# 5V_Supply.net
KiCad netlist of a schematic drawn in Altium Designer
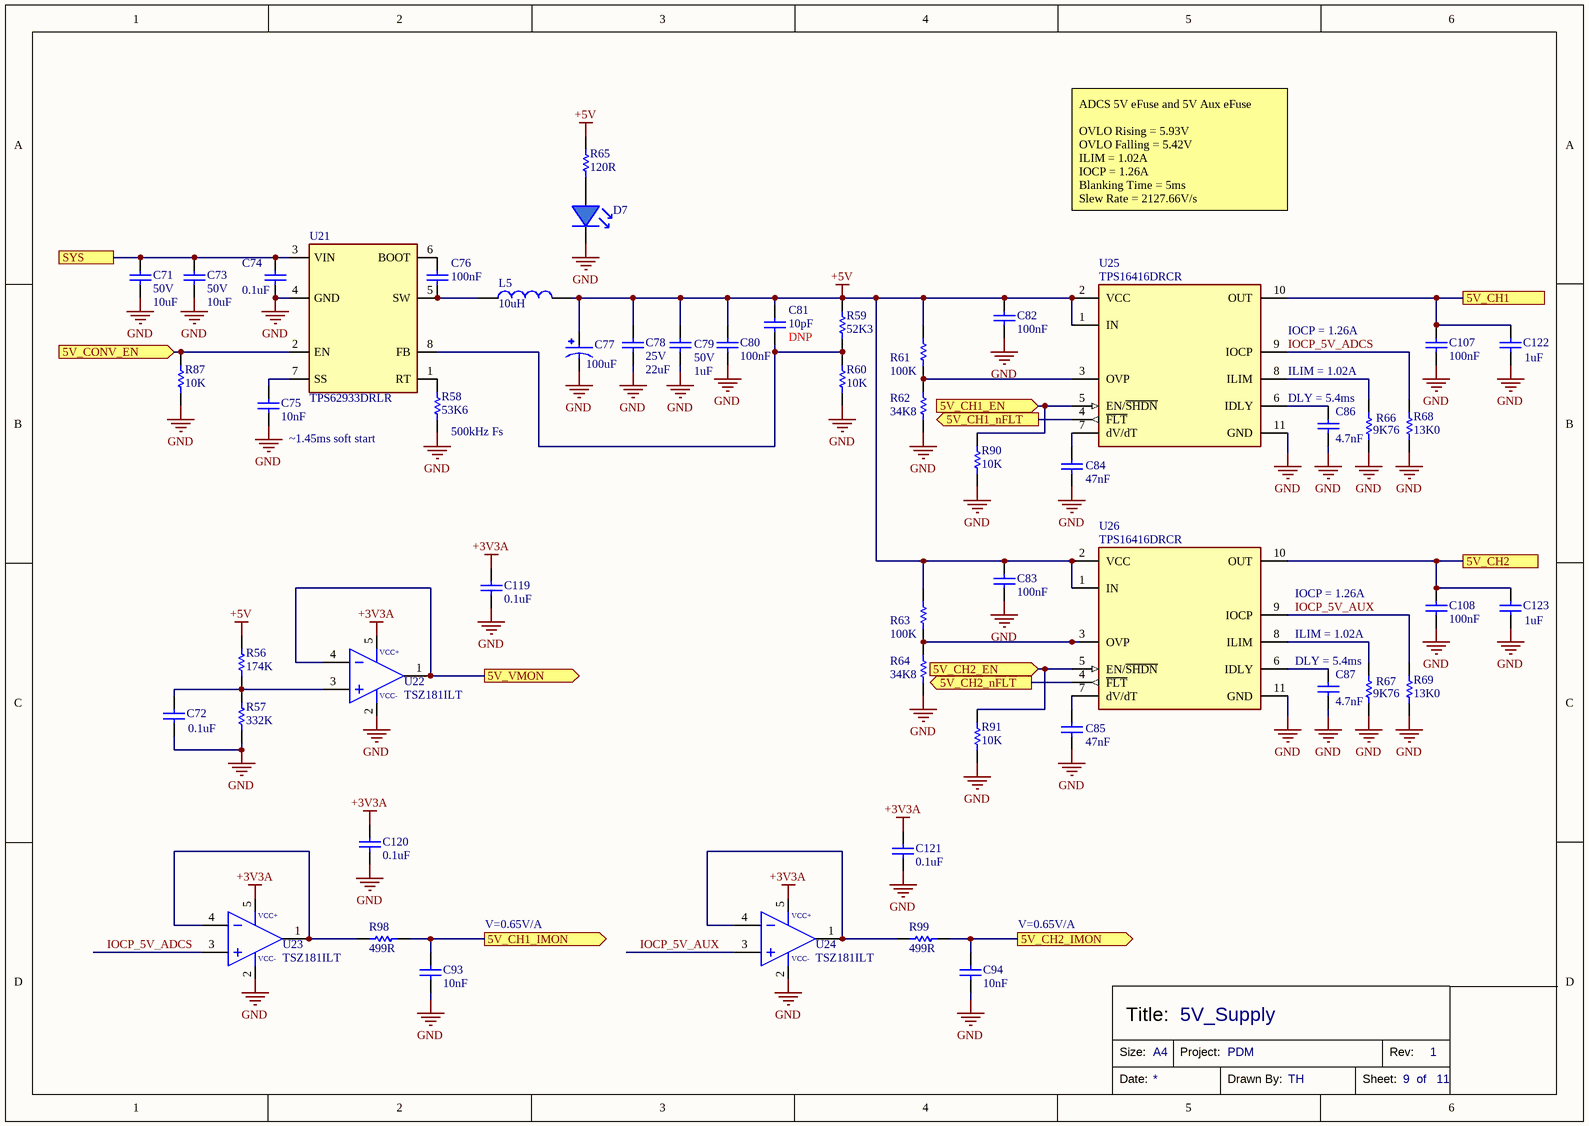
[diagram p0: 5V_Supply.SchDoc]

(export (version "E")
  (design (tool "Eeschema 10.0.6"))
  (components
    (comp (ref "C71")
      (value "CL32B106KBJNNNE")
      (footprint "CAPC1210X090")
      (description "10 µF ±10% 50V Ceramic Capacitor X7R 1210 (3225 Metric)")
      (fields
        (field (name "DISTRIBUTOR PART NUMBER") "1276-3387-1-ND")
        (field (name "TOLERANCE") "10%")
        (field (name "VOLTAGE RATING") "50V")
        (field (name "CAPACITANCE") "10uF")
      )
      (libsource (lib "Ahristi_Library") (part "CL32B106KBJNNNE"))
    )
    (comp (ref "C72")
      (value "CL21B104KACNNNC")
      (footprint "CAPC0805X060")
      (description "0.1uF ±10% 25V Ceramic Capacitor X7R 0805 (2012 Metric)")
      (fields
        (field (name "DISTRIBUTOR PART NUMBER") "1276-1099-1-ND")
        (field (name "TOLERANCE") "10%")
        (field (name "CAPACITANCE") "0.1uF")
      )
      (libsource (lib "Ahristi_Library") (part "CL21B104KACNNNC"))
    )
    (comp (ref "C73")
      (value "CL32B106KBJNNNE")
      (footprint "CAPC1210X090")
      (description "10 µF ±10% 50V Ceramic Capacitor X7R 1210 (3225 Metric)")
      (fields
        (field (name "DISTRIBUTOR PART NUMBER") "1276-3387-1-ND")
        (field (name "TOLERANCE") "10%")
        (field (name "VOLTAGE RATING") "50V")
        (field (name "CAPACITANCE") "10uF")
      )
      (libsource (lib "Ahristi_Library") (part "CL32B106KBJNNNE"))
    )
    (comp (ref "C74")
      (value "CL05B104KB5NNNC")
      (footprint "CAPC0402X020")
      (description "0.1 µF ±10% 50V Ceramic Capacitor X7R 0402 (1005 Metric)")
      (fields
        (field (name "TOLERANCE") "10%")
        (field (name "DISTRIBUTOR PART NUMBER") "1276-CL05B104KB5NNNCCT-ND")
        (field (name "CAPACITANCE") "0.1uF")
      )
      (libsource (lib "Ahristi_Library") (part "CL05B104KB5NNNC"))
    )
    (comp (ref "C75")
      (value "CL21B103KBANNNC")
      (footprint "CAPC0805X060")
      (description "10nF ±10% 50V Ceramic Capacitor X7R 0805 (2012 Metric)")
      (fields
        (field (name "DISTRIBUTOR PART NUMBER") "1276-1015-1-ND")
        (field (name "TOLERANCE") "10%")
        (field (name "CAPACITANCE") "10nF")
      )
      (libsource (lib "Ahristi_Library") (part "CL21B103KBANNNC"))
    )
    (comp (ref "C76")
      (value "C0603C104K5RACTU")
      (footprint "CAPC0603X040")
      (description "0.1 µF ±10% 50V Ceramic Capacitor X7R 0603 (1608 Metric)")
      (fields
        (field (name "DISTRIBUTOR PART NUMBER") "399-C0603C104K5RACTUCT-ND")
        (field (name "TOLERANCE") "10%")
        (field (name "CAPACITANCE") "100nF")
      )
      (libsource (lib "Ahristi_Library") (part "C0603C104K5RACTU"))
    )
    (comp (ref "C77")
      (value "TPSC107K010R0100")
      (footprint "2312 Tantalum")
      (description "100 µF Molded Tantalum Capacitors 10 V 2312 (6032 Metric) 100mOhm")
      (fields (field (name "DISTRIBUTOR PART NUMBER") "478-1765-1-ND") (field (name "CAPACITANCE") "100uF"))
      (libsource (lib "Ahristi_Library") (part "TPSC107K010R0100"))
    )
    (comp (ref "C78")
      (value "CL32B226KAJNNNE")
      (footprint "CAPC1210X090")
      (description "22 µF ±10% 25V Ceramic Capacitor X7R 1210 (3225 Metric)")
      (fields
        (field (name "DISTRIBUTOR PART NUMBER") "1276-3392-1-ND")
        (field (name "TOLERANCE") "10%")
        (field (name "VOLTAGE RATING") "25V")
        (field (name "CAPACITANCE") "22uF")
      )
      (libsource (lib "Ahristi_Library") (part "CL32B226KAJNNNE"))
    )
    (comp (ref "C79")
      (value "CL21B105KBFNNNE")
      (footprint "CAPC0805X060")
      (description "1uF 50V X7R ±10% 0805 Multilayer Ceramic Capacitors MLCC - SMD/SMT ROHS")
      (fields
        (field (name "DISTRIBUTOR PART NUMBER") "1276-1029-1-ND")
        (field (name "TOLERANCE") "10%")
        (field (name "VOLTAGE RATING") "50V")
        (field (name "CAPACITANCE") "1uF")
      )
      (libsource (lib "Ahristi_Library") (part "CL21B105KBFNNNE"))
    )
    (comp (ref "C80")
      (value "C0603C104K5RACTU")
      (footprint "CAPC0603X040")
      (description "0.1 µF ±10% 50V Ceramic Capacitor X7R 0603 (1608 Metric)")
      (fields
        (field (name "DISTRIBUTOR PART NUMBER") "399-C0603C104K5RACTUCT-ND")
        (field (name "TOLERANCE") "10%")
        (field (name "CAPACITANCE") "100nF")
      )
      (libsource (lib "Ahristi_Library") (part "C0603C104K5RACTU"))
    )
    (comp (ref "C81")
      (value "C0603C104K5RACTU")
      (footprint "CAPC0603X040")
      (description "10 pF ±5% 50V Ceramic Capacitor C0G, NP0 0603 (1608 Metric)")
      (fields
        (field (name "PART NUMBER") "C0603C100J5GACTU")
        (field (name "DISTRIBUTOR PART NUMBER") "399-C0603C100J5GACTUCT-ND")
        (field (name "CAPACITANCE") "10pF")
      )
      (libsource (lib "Ahristi_Library") (part "C0603C100J5GACTU"))
    )
    (comp (ref "C82")
      (value "C0603C104K5RACTU")
      (footprint "CAPC0603X040")
      (description "0.1 µF ±10% 50V Ceramic Capacitor X7R 0603 (1608 Metric)")
      (fields
        (field (name "DISTRIBUTOR PART NUMBER") "399-C0603C104K5RACTUCT-ND")
        (field (name "TOLERANCE") "10%")
        (field (name "CAPACITANCE") "100nF")
      )
      (libsource (lib "Ahristi_Library") (part "C0603C104K5RACTU"))
    )
    (comp (ref "C83")
      (value "C0603C104K5RACTU")
      (footprint "CAPC0603X040")
      (description "0.1 µF ±10% 50V Ceramic Capacitor X7R 0603 (1608 Metric)")
      (fields
        (field (name "DISTRIBUTOR PART NUMBER") "399-C0603C104K5RACTUCT-ND")
        (field (name "TOLERANCE") "10%")
        (field (name "CAPACITANCE") "100nF")
      )
      (libsource (lib "Ahristi_Library") (part "C0603C104K5RACTU"))
    )
    (comp (ref "C84")
      (value "CL21B473KBCNNNC")
      (footprint "CAPC0805X060")
      (description "0.047 µF ±10% 50V Ceramic Capacitor X7R 0805 (2012 Metric)")
      (fields
        (field (name "DISTRIBUTOR PART NUMBER") "1276-1250-1-ND")
        (field (name "TOLERANCE") "10%")
        (field (name "CAPACITANCE") "47nF")
      )
      (libsource (lib "Ahristi_Library") (part "CL21B473KBCNNNC"))
    )
    (comp (ref "C85")
      (value "CL21B473KBCNNNC")
      (footprint "CAPC0805X060")
      (description "0.047 µF ±10% 50V Ceramic Capacitor X7R 0805 (2012 Metric)")
      (fields
        (field (name "DISTRIBUTOR PART NUMBER") "1276-1250-1-ND")
        (field (name "TOLERANCE") "10%")
        (field (name "CAPACITANCE") "47nF")
      )
      (libsource (lib "Ahristi_Library") (part "CL21B473KBCNNNC"))
    )
    (comp (ref "C86")
      (value "CL21B105KAFNNNE")
      (footprint "CAPC0805X060")
      (description "4.7nF ±10% 50V Ceramic Capacitor X7R 0805 (2012 Metric)")
      (fields
        (field (name "PART NUMBER") "CL21B472KBANNNC")
        (field (name "DISTRIBUTOR PART NUMBER") "1276-1155-1-ND")
        (field (name "CAPACITANCE") "4.7nF")
      )
      (libsource (lib "Ahristi_Library") (part "CL21B472KBANNNC"))
    )
    (comp (ref "C87")
      (value "CL21B105KAFNNNE")
      (footprint "CAPC0805X060")
      (description "4.7nF ±10% 50V Ceramic Capacitor X7R 0805 (2012 Metric)")
      (fields
        (field (name "PART NUMBER") "CL21B472KBANNNC")
        (field (name "DISTRIBUTOR PART NUMBER") "1276-1155-1-ND")
        (field (name "CAPACITANCE") "4.7nF")
      )
      (libsource (lib "Ahristi_Library") (part "CL21B472KBANNNC"))
    )
    (comp (ref "C93")
      (value "CL21B103KBANNNC")
      (footprint "CAPC0805X060")
      (description "10nF ±10% 50V Ceramic Capacitor X7R 0805 (2012 Metric)")
      (fields
        (field (name "DISTRIBUTOR PART NUMBER") "1276-1015-1-ND")
        (field (name "TOLERANCE") "10%")
        (field (name "CAPACITANCE") "10nF")
      )
      (libsource (lib "Ahristi_Library") (part "CL21B103KBANNNC"))
    )
    (comp (ref "C94")
      (value "CL21B103KBANNNC")
      (footprint "CAPC0805X060")
      (description "10nF ±10% 50V Ceramic Capacitor X7R 0805 (2012 Metric)")
      (fields
        (field (name "DISTRIBUTOR PART NUMBER") "1276-1015-1-ND")
        (field (name "TOLERANCE") "10%")
        (field (name "CAPACITANCE") "10nF")
      )
      (libsource (lib "Ahristi_Library") (part "CL21B103KBANNNC"))
    )
    (comp (ref "C107")
      (value "C0603C104K5RACTU")
      (footprint "CAPC0603X040")
      (description "0.1 µF ±10% 50V Ceramic Capacitor X7R 0603 (1608 Metric)")
      (fields
        (field (name "DISTRIBUTOR PART NUMBER") "399-C0603C104K5RACTUCT-ND")
        (field (name "TOLERANCE") "10%")
        (field (name "CAPACITANCE") "100nF")
      )
      (libsource (lib "Ahristi_Library") (part "C0603C104K5RACTU"))
    )
    (comp (ref "C108")
      (value "C0603C104K5RACTU")
      (footprint "CAPC0603X040")
      (description "0.1 µF ±10% 50V Ceramic Capacitor X7R 0603 (1608 Metric)")
      (fields
        (field (name "DISTRIBUTOR PART NUMBER") "399-C0603C104K5RACTUCT-ND")
        (field (name "TOLERANCE") "10%")
        (field (name "CAPACITANCE") "100nF")
      )
      (libsource (lib "Ahristi_Library") (part "C0603C104K5RACTU"))
    )
    (comp (ref "C119")
      (value "C0603C104K5RACTU")
      (footprint "CAPC0603X040")
      (description "0.1 µF ±10% 50V Ceramic Capacitor X7R 0603 (1608 Metric)")
      (fields
        (field (name "DISTRIBUTOR PART NUMBER") "399-C0603C104K5RACTUCT-ND")
        (field (name "TOLERANCE") "10%")
        (field (name "CAPACITANCE") "0.1uF")
      )
      (libsource (lib "Ahristi_Library") (part "C0603C104K5RACTU"))
    )
    (comp (ref "C120")
      (value "C0603C104K5RACTU")
      (footprint "CAPC0603X040")
      (description "0.1 µF ±10% 50V Ceramic Capacitor X7R 0603 (1608 Metric)")
      (fields
        (field (name "DISTRIBUTOR PART NUMBER") "399-C0603C104K5RACTUCT-ND")
        (field (name "TOLERANCE") "10%")
        (field (name "CAPACITANCE") "0.1uF")
      )
      (libsource (lib "Ahristi_Library") (part "C0603C104K5RACTU"))
    )
    (comp (ref "C121")
      (value "C0603C104K5RACTU")
      (footprint "CAPC0603X040")
      (description "0.1 µF ±10% 50V Ceramic Capacitor X7R 0603 (1608 Metric)")
      (fields
        (field (name "DISTRIBUTOR PART NUMBER") "399-C0603C104K5RACTUCT-ND")
        (field (name "TOLERANCE") "10%")
        (field (name "CAPACITANCE") "0.1uF")
      )
      (libsource (lib "Ahristi_Library") (part "C0603C104K5RACTU"))
    )
    (comp (ref "C122")
      (value "CL21B105KAFNNNE")
      (footprint "CAPC0805X060")
      (description "1uF ±10% 25V Ceramic Capacitor X7R 0805 (2012 Metric)")
      (fields
        (field (name "DISTRIBUTOR PART NUMBER") "1276-1066-1-ND")
        (field (name "TOLERANCE") "10%")
        (field (name "CAPACITANCE") "1uF")
      )
      (libsource (lib "Ahristi_Library") (part "CL21B105KAFNNNE"))
    )
    (comp (ref "C123")
      (value "CL21B105KAFNNNE")
      (footprint "CAPC0805X060")
      (description "1uF ±10% 25V Ceramic Capacitor X7R 0805 (2012 Metric)")
      (fields
        (field (name "DISTRIBUTOR PART NUMBER") "1276-1066-1-ND")
        (field (name "TOLERANCE") "10%")
        (field (name "CAPACITANCE") "1uF")
      )
      (libsource (lib "Ahristi_Library") (part "CL21B105KAFNNNE"))
    )
    (comp (ref "D7")
      (value "LSM0805463V")
      (footprint "LEDB_0805")
      (description "Blue 469nm LED Indication - Discrete 3V 0805 (2012 Metric)")
      (fields (field (name "DISTRIBUTOR PART NUMBER") "28-LSM0805463VCT-ND"))
      (libsource (lib "Ahristi_Library") (part "LEDB0805"))
    )
    (comp (ref "L5")
      (value "1274AS-H-100M=P3")
      (footprint "1274AS-H-100M=P3")
      (description "Inductor 10 µH , 4.4 A 30.4mOhm Max Shielded Drum Core")
      (fields (field (name "DISTRIBUTOR PART NUMBER") "490-10846-1-ND") (field (name "INDUCTANCE") "10uH"))
      (libsource (lib "Ahristi_Library") (part "1274AS-H-100M=P3"))
    )
    (comp (ref "R56")
      (value "RMCF0603FT174K")
      (footprint "RESC0603")
      (description "174 kOhms ±1% 0.1W, 1/10W Chip Resistor 0603 (1608 Metric) Automotive AEC-Q200 Thick Film")
      (fields
        (field (name "TOLERANCE") "1%")
        (field (name "DISTRIBUTOR PART NUMBER") "RMCF0603FT174KCT-ND")
        (field (name "RESISTANCE") "174K")
      )
      (libsource (lib "Ahristi_Library") (part "RMCF0603FT174K"))
    )
    (comp (ref "R57")
      (value "RMCF0805FT332K")
      (footprint "RESC0805")
      (description "332 kOhms ±1% 0.125W, 1/8W Chip Resistor 0805 (2012 Metric) Automotive AEC-Q200 Thick Film")
      (fields
        (field (name "TOLERANCE") "1%")
        (field (name "DISTRIBUTOR PART NUMBER") "RMCF0805FT332KCT-ND")
        (field (name "RESISTANCE") "332K")
      )
      (libsource (lib "Ahristi_Library") (part "RMCF0805FT332K"))
    )
    (comp (ref "R58")
      (value "RMCF0805FT53K6")
      (footprint "RESC0805")
      (description "53.6 kOhms ±1% 0.125W, 1/8W Chip Resistor 0805 (2012 Metric) Automotive AEC-Q200 Thick Film")
      (fields
        (field (name "TOLERANCE") "1%")
        (field (name "DISTRIBUTOR PART NUMBER") "RMCF0805FT53K6CT-ND")
        (field (name "RESISTANCE") "53K6")
      )
      (libsource (lib "Ahristi_Library") (part "RMCF0805FT53K6"))
    )
    (comp (ref "R59")
      (value "RMCF0603FT52K3")
      (footprint "RESC0603")
      (description "52.3 kOhms ±1% 0.1W, 1/10W Chip Resistor 0603 (1608 Metric) Automotive AEC-Q200 Thick Film")
      (fields
        (field (name "TOLERANCE") "1%")
        (field (name "DISTRIBUTOR PART NUMBER") "RMCF0603FT174KCT-ND")
        (field (name "RESISTANCE") "52K3")
      )
      (libsource (lib "Ahristi_Library") (part "RMCF0603FT52K3"))
    )
    (comp (ref "R60")
      (value "RMCF0603FT10K0")
      (footprint "RESC0603")
      (description "10 kOhms ±1% 0.1W, 1/10W Chip Resistor 0603 (1608 Metric) Automotive AEC-Q200 Thick Film")
      (fields
        (field (name "TOLERANCE") "1%")
        (field (name "DISTRIBUTOR PART NUMBER") "RMCF0603FT10K0CT-ND")
        (field (name "RESISTANCE") "10K")
      )
      (libsource (lib "Ahristi_Library") (part "RMCF0603FT10K0"))
    )
    (comp (ref "R61")
      (value "RMCF0805FG100K")
      (footprint "RESC0805")
      (description "100 kOhms ±1% 0.125W, 1/8W Chip Resistor 0805 (2012 Metric) Automotive AEC-Q200 Thick Film")
      (fields
        (field (name "TOLERANCE") "1%")
        (field (name "DISTRIBUTOR PART NUMBER") "RMCF0805FG100KCT-ND")
        (field (name "RESISTANCE") "100K")
      )
      (libsource (lib "Ahristi_Library") (part "RMCF0805FG100K"))
    )
    (comp (ref "R62")
      (value "RMCF0805FT34K8")
      (footprint "RESC0805")
      (description "34.8 kOhms ±1% 0.125W, 1/8W Chip Resistor 0805 (2012 Metric) Automotive AEC-Q200 Thick Film")
      (fields
        (field (name "TOLERANCE") "1%")
        (field (name "DISTRIBUTOR PART NUMBER") "RMCF0805FT34K8CT-ND")
        (field (name "RESISTANCE") "34K8")
      )
      (libsource (lib "Ahristi_Library") (part "RMCF0805FT34K8"))
    )
    (comp (ref "R63")
      (value "RMCF0805FG100K")
      (footprint "RESC0805")
      (description "100 kOhms ±1% 0.125W, 1/8W Chip Resistor 0805 (2012 Metric) Automotive AEC-Q200 Thick Film")
      (fields
        (field (name "TOLERANCE") "1%")
        (field (name "DISTRIBUTOR PART NUMBER") "RMCF0805FG100KCT-ND")
        (field (name "RESISTANCE") "100K")
      )
      (libsource (lib "Ahristi_Library") (part "RMCF0805FG100K"))
    )
    (comp (ref "R64")
      (value "RMCF0805FT34K8")
      (footprint "RESC0805")
      (description "34.8 kOhms ±1% 0.125W, 1/8W Chip Resistor 0805 (2012 Metric) Automotive AEC-Q200 Thick Film")
      (fields
        (field (name "TOLERANCE") "1%")
        (field (name "DISTRIBUTOR PART NUMBER") "RMCF0805FT34K8CT-ND")
        (field (name "RESISTANCE") "34K8")
      )
      (libsource (lib "Ahristi_Library") (part "RMCF0805FT34K8"))
    )
    (comp (ref "R65")
      (value "RMCF0805FT120R")
      (footprint "RESC0805")
      (description "120 Ohms ±1% 0.125W, 1/8W Chip Resistor 0805 (2012 Metric) Automotive AEC-Q200 Thick Film")
      (fields
        (field (name "TOLERANCE") "1%")
        (field (name "DISTRIBUTOR PART NUMBER") "738-RMCF0805FT120RCT-ND")
        (field (name "RESISTANCE") "120R")
      )
      (libsource (lib "Ahristi_Library") (part "RMCF0805FT120R"))
    )
    (comp (ref "R66")
      (value "RMCF0805FT9K76")
      (footprint "RESC0805")
      (description "9.76 kOhms ±1% 0.125W, 1/8W Chip Resistor 0805 (2012 Metric) Automotive AEC-Q200 Thick Film")
      (fields
        (field (name "TOLERANCE") "1%")
        (field (name "DISTRIBUTOR PART NUMBER") "RMCF0805FT9K76CT-ND")
        (field (name "RESISTANCE") "9K76")
      )
      (libsource (lib "Ahristi_Library") (part "RMCF0805FT9K76"))
    )
    (comp (ref "R67")
      (value "RMCF0805FT9K76")
      (footprint "RESC0805")
      (description "9.76 kOhms ±1% 0.125W, 1/8W Chip Resistor 0805 (2012 Metric) Automotive AEC-Q200 Thick Film")
      (fields
        (field (name "TOLERANCE") "1%")
        (field (name "DISTRIBUTOR PART NUMBER") "RMCF0805FT9K76CT-ND")
        (field (name "RESISTANCE") "9K76")
      )
      (libsource (lib "Ahristi_Library") (part "RMCF0805FT9K76"))
    )
    (comp (ref "R68")
      (value "RMCF0805FT13K0")
      (footprint "RESC0805")
      (description "13 kOhms ±1% 0.125W, 1/8W Chip Resistor 0805 (2012 Metric) Automotive AEC-Q200 Thick Film")
      (fields
        (field (name "TOLERANCE") "1%")
        (field (name "DISTRIBUTOR PART NUMBER") "RMCF0805FT13K0CT-ND")
        (field (name "RESISTANCE") "13K0")
      )
      (libsource (lib "Ahristi_Library") (part "RMCF0805FT13K0"))
    )
    (comp (ref "R69")
      (value "RMCF0805FT13K0")
      (footprint "RESC0805")
      (description "13 kOhms ±1% 0.125W, 1/8W Chip Resistor 0805 (2012 Metric) Automotive AEC-Q200 Thick Film")
      (fields
        (field (name "TOLERANCE") "1%")
        (field (name "DISTRIBUTOR PART NUMBER") "RMCF0805FT13K0CT-ND")
        (field (name "RESISTANCE") "13K0")
      )
      (libsource (lib "Ahristi_Library") (part "RMCF0805FT13K0"))
    )
    (comp (ref "R87")
      (value "RMCF0805FT10K0")
      (footprint "RESC0805")
      (description "10 kOhms ±1% 0.125W, 1/8W Chip Resistor 0805 (2012 Metric) Automotive AEC-Q200 Thick Film")
      (fields
        (field (name "TOLERANCE") "1%")
        (field (name "DISTRIBUTOR PART NUMBER") "RMCF0805FT10K0CT-ND")
        (field (name "RESISTANCE") "10K")
      )
      (libsource (lib "Ahristi_Library") (part "RMCF0805FT10K0"))
    )
    (comp (ref "R90")
      (value "RMCF0805FT10K0")
      (footprint "RESC0805")
      (description "10 kOhms ±1% 0.125W, 1/8W Chip Resistor 0805 (2012 Metric) Automotive AEC-Q200 Thick Film")
      (fields
        (field (name "TOLERANCE") "1%")
        (field (name "DISTRIBUTOR PART NUMBER") "RMCF0805FT10K0CT-ND")
        (field (name "RESISTANCE") "10K")
      )
      (libsource (lib "Ahristi_Library") (part "RMCF0805FT10K0"))
    )
    (comp (ref "R91")
      (value "RMCF0805FT10K0")
      (footprint "RESC0805")
      (description "10 kOhms ±1% 0.125W, 1/8W Chip Resistor 0805 (2012 Metric) Automotive AEC-Q200 Thick Film")
      (fields
        (field (name "TOLERANCE") "1%")
        (field (name "DISTRIBUTOR PART NUMBER") "RMCF0805FT10K0CT-ND")
        (field (name "RESISTANCE") "10K")
      )
      (libsource (lib "Ahristi_Library") (part "RMCF0805FT10K0"))
    )
    (comp (ref "R98")
      (value "RMCF0805FT499R")
      (footprint "RESC0805")
      (description "499 Ohms ±1% 0.125W, 1/8W Chip Resistor 0805 (2012 Metric) Automotive AEC-Q200 Thick Film")
      (fields
        (field (name "TOLERANCE") "1%")
        (field (name "DISTRIBUTOR PART NUMBER") "RMCF0805FT499RCT-ND")
        (field (name "RESISTANCE") "499R")
      )
      (libsource (lib "Ahristi_Library") (part "RMCF0805FT499R"))
    )
    (comp (ref "R99")
      (value "RMCF0805FT499R")
      (footprint "RESC0805")
      (description "499 Ohms ±1% 0.125W, 1/8W Chip Resistor 0805 (2012 Metric) Automotive AEC-Q200 Thick Film")
      (fields
        (field (name "TOLERANCE") "1%")
        (field (name "DISTRIBUTOR PART NUMBER") "RMCF0805FT499RCT-ND")
        (field (name "RESISTANCE") "499R")
      )
      (libsource (lib "Ahristi_Library") (part "RMCF0805FT499R"))
    )
    (comp (ref "U21")
      (value "TPS62933DRLR")
      (footprint "SOT-583")
      (description "Buck Switching Regulator IC Positive Adjustable 0.8V 1 Output 3A SOT-583")
      (fields (field (name "DISTRIBUTOR PART NUMBER") "296-TPS62933DRLRCT-ND"))
      (libsource (lib "Ahristi_Library") (part "TPS62933DRLR"))
    )
    (comp (ref "U22")
      (value "TSZ181ILT")
      (footprint "SOT23-5 IC")
      (description "Operational Amplifier, General Purpose, 2.2V~5.5V")
      (fields (field (name "DISTRIBUTOR PART NUMBER") "497-18084-1-ND"))
      (libsource (lib "Ahristi_Library") (part "TSZ181ILT"))
    )
    (comp (ref "U23")
      (value "TSZ181ILT")
      (footprint "SOT23-5 IC")
      (description "Operational Amplifier, General Purpose, 2.2V~5.5V")
      (fields (field (name "DISTRIBUTOR PART NUMBER") "497-18084-1-ND"))
      (libsource (lib "Ahristi_Library") (part "TSZ181ILT"))
    )
    (comp (ref "U24")
      (value "TSZ181ILT")
      (footprint "SOT23-5 IC")
      (description "Operational Amplifier, General Purpose, 2.2V~5.5V")
      (fields (field (name "DISTRIBUTOR PART NUMBER") "497-18084-1-ND"))
      (libsource (lib "Ahristi_Library") (part "TSZ181ILT"))
    )
    (comp (ref "U25")
      (value "TPS16410DRCR")
      (footprint "TPS1641")
      (description "2.7-V to 40-V 152-mΩ 1.8-A eFuse with output power limiting")
      (fields
        (field (name "DISTRIBUTOR PART NUMBER") "296-TPS16410DRCRCT-ND")
        (field (name "PART NUMBER") "TPS16416DRCR")
      )
      (libsource (lib "Ahristi_Library") (part "TPS16410DRCR"))
    )
    (comp (ref "U26")
      (value "TPS16410DRCR")
      (footprint "TPS1641")
      (description "2.7-V to 40-V 152-mΩ 1.8-A eFuse with output power limiting")
      (fields
        (field (name "DISTRIBUTOR PART NUMBER") "296-TPS16410DRCRCT-ND")
        (field (name "PART NUMBER") "TPS16416DRCR")
      )
      (libsource (lib "Ahristi_Library") (part "TPS16410DRCR"))
    )
  )
  (nets
    (net (code "1") (name "+3V3A") (class "Default")
      (node (ref "C119") (pin "2") (pinfunction "2_2") (pintype "passive"))
      (node (ref "C120") (pin "2") (pinfunction "2_2") (pintype "passive"))
      (node (ref "C121") (pin "2") (pinfunction "2_2") (pintype "passive"))
      (node (ref "U22") (pin "5") (pinfunction "VCC+_5") (pintype "power_in"))
      (node (ref "U23") (pin "5") (pinfunction "VCC+_5") (pintype "power_in"))
      (node (ref "U24") (pin "5") (pinfunction "VCC+_5") (pintype "power_in"))
    )
    (net (code "2") (name "+5V") (class "Default")
      (node (ref "C77") (pin "1") (pinfunction "1_1") (pintype "passive"))
      (node (ref "C78") (pin "2") (pinfunction "2_2") (pintype "passive"))
      (node (ref "C79") (pin "2") (pinfunction "2_2") (pintype "passive"))
      (node (ref "C80") (pin "2") (pinfunction "2_2") (pintype "passive"))
      (node (ref "C81") (pin "2") (pinfunction "2_2") (pintype "passive"))
      (node (ref "C82") (pin "2") (pinfunction "2_2") (pintype "passive"))
      (node (ref "C83") (pin "2") (pinfunction "2_2") (pintype "passive"))
      (node (ref "L5") (pin "2") (pinfunction "2_2") (pintype "passive"))
      (node (ref "R56") (pin "2") (pinfunction "2_2") (pintype "passive"))
      (node (ref "R59") (pin "2") (pinfunction "2_2") (pintype "passive"))
      (node (ref "R61") (pin "2") (pinfunction "2_2") (pintype "passive"))
      (node (ref "R63") (pin "2") (pinfunction "2_2") (pintype "passive"))
      (node (ref "R65") (pin "2") (pinfunction "2_2") (pintype "passive"))
      (node (ref "U25") (pin "1") (pinfunction "IN_1") (pintype "passive"))
      (node (ref "U25") (pin "2") (pinfunction "VCC_2") (pintype "passive"))
      (node (ref "U26") (pin "1") (pinfunction "IN_1") (pintype "passive"))
      (node (ref "U26") (pin "2") (pinfunction "VCC_2") (pintype "passive"))
    )
    (net (code "3") (name "/5V_CH1") (class "Default")
      (node (ref "C107") (pin "2") (pinfunction "2_2") (pintype "passive"))
      (node (ref "C122") (pin "2") (pinfunction "2_2") (pintype "passive"))
      (node (ref "U25") (pin "10") (pinfunction "OUT_10") (pintype "passive"))
    )
    (net (code "4") (name "/5V_CH1_EN") (class "Default")
      (node (ref "R90") (pin "2") (pinfunction "2_2") (pintype "passive"))
      (node (ref "U25") (pin "5") (pinfunction "EN/~{SHDN}_5") (pintype "input"))
    )
    (net (code "5") (name "/5V_CH1_IMON") (class "Default")
      (node (ref "C93") (pin "2") (pinfunction "2_2") (pintype "passive"))
      (node (ref "R98") (pin "2") (pinfunction "2_2") (pintype "passive"))
    )
    (net (code "6") (name "/5V_CH1_nFLT") (class "Default")
      (node (ref "U25") (pin "4") (pinfunction "~{FLT}_4") (pintype "output"))
    )
    (net (code "7") (name "/5V_CH2") (class "Default")
      (node (ref "C108") (pin "2") (pinfunction "2_2") (pintype "passive"))
      (node (ref "C123") (pin "2") (pinfunction "2_2") (pintype "passive"))
      (node (ref "U26") (pin "10") (pinfunction "OUT_10") (pintype "passive"))
    )
    (net (code "8") (name "/5V_CH2_EN") (class "Default")
      (node (ref "R91") (pin "2") (pinfunction "2_2") (pintype "passive"))
      (node (ref "U26") (pin "5") (pinfunction "EN/~{SHDN}_5") (pintype "input"))
    )
    (net (code "9") (name "/5V_CH2_IMON") (class "Default")
      (node (ref "C94") (pin "2") (pinfunction "2_2") (pintype "passive"))
      (node (ref "R99") (pin "2") (pinfunction "2_2") (pintype "passive"))
    )
    (net (code "10") (name "/5V_CH2_nFLT") (class "Default")
      (node (ref "U26") (pin "4") (pinfunction "~{FLT}_4") (pintype "output"))
    )
    (net (code "11") (name "/5V_CONV_EN") (class "Default")
      (node (ref "R87") (pin "2") (pinfunction "2_2") (pintype "passive"))
      (node (ref "U21") (pin "2") (pinfunction "EN_2") (pintype "passive"))
    )
    (net (code "12") (name "/5V_VMON") (class "Default")
      (node (ref "U22") (pin "1") (pinfunction "OUT_1") (pintype "passive"))
      (node (ref "U22") (pin "4") (pinfunction "IN-_4") (pintype "passive"))
    )
    (net (code "13") (name "/IOCP_5V_ADCS") (class "Default")
      (node (ref "R68") (pin "2") (pinfunction "2_2") (pintype "passive"))
      (node (ref "U23") (pin "3") (pinfunction "IN+_3") (pintype "passive"))
      (node (ref "U25") (pin "9") (pinfunction "IOCP_9") (pintype "passive"))
    )
    (net (code "14") (name "/IOCP_5V_AUX") (class "Default")
      (node (ref "R69") (pin "2") (pinfunction "2_2") (pintype "passive"))
      (node (ref "U24") (pin "3") (pinfunction "IN+_3") (pintype "passive"))
      (node (ref "U26") (pin "9") (pinfunction "IOCP_9") (pintype "passive"))
    )
    (net (code "15") (name "/SYS") (class "Default")
      (node (ref "C71") (pin "2") (pinfunction "2_2") (pintype "passive"))
      (node (ref "C73") (pin "2") (pinfunction "2_2") (pintype "passive"))
      (node (ref "C74") (pin "2") (pinfunction "2_2") (pintype "passive"))
      (node (ref "U21") (pin "3") (pinfunction "VIN_3") (pintype "passive"))
    )
    (net (code "16") (name "GND") (class "Default")
      (node (ref "C107") (pin "1") (pinfunction "1_1") (pintype "passive"))
      (node (ref "C108") (pin "1") (pinfunction "1_1") (pintype "passive"))
      (node (ref "C119") (pin "1") (pinfunction "1_1") (pintype "passive"))
      (node (ref "C120") (pin "1") (pinfunction "1_1") (pintype "passive"))
      (node (ref "C121") (pin "1") (pinfunction "1_1") (pintype "passive"))
      (node (ref "C122") (pin "1") (pinfunction "1_1") (pintype "passive"))
      (node (ref "C123") (pin "1") (pinfunction "1_1") (pintype "passive"))
      (node (ref "C71") (pin "1") (pinfunction "1_1") (pintype "passive"))
      (node (ref "C72") (pin "1") (pinfunction "1_1") (pintype "passive"))
      (node (ref "C73") (pin "1") (pinfunction "1_1") (pintype "passive"))
      (node (ref "C74") (pin "1") (pinfunction "1_1") (pintype "passive"))
      (node (ref "C75") (pin "1") (pinfunction "1_1") (pintype "passive"))
      (node (ref "C77") (pin "2") (pinfunction "2_2") (pintype "passive"))
      (node (ref "C78") (pin "1") (pinfunction "1_1") (pintype "passive"))
      (node (ref "C79") (pin "1") (pinfunction "1_1") (pintype "passive"))
      (node (ref "C80") (pin "1") (pinfunction "1_1") (pintype "passive"))
      (node (ref "C82") (pin "1") (pinfunction "1_1") (pintype "passive"))
      (node (ref "C83") (pin "1") (pinfunction "1_1") (pintype "passive"))
      (node (ref "C84") (pin "1") (pinfunction "1_1") (pintype "passive"))
      (node (ref "C85") (pin "1") (pinfunction "1_1") (pintype "passive"))
      (node (ref "C86") (pin "1") (pinfunction "1_1") (pintype "passive"))
      (node (ref "C87") (pin "1") (pinfunction "1_1") (pintype "passive"))
      (node (ref "C93") (pin "1") (pinfunction "1_1") (pintype "passive"))
      (node (ref "C94") (pin "1") (pinfunction "1_1") (pintype "passive"))
      (node (ref "D7") (pin "K") (pinfunction "K_K") (pintype "passive"))
      (node (ref "R57") (pin "1") (pinfunction "1_1") (pintype "passive"))
      (node (ref "R58") (pin "1") (pinfunction "1_1") (pintype "passive"))
      (node (ref "R60") (pin "1") (pinfunction "1_1") (pintype "passive"))
      (node (ref "R62") (pin "1") (pinfunction "1_1") (pintype "passive"))
      (node (ref "R64") (pin "1") (pinfunction "1_1") (pintype "passive"))
      (node (ref "R66") (pin "1") (pinfunction "1_1") (pintype "passive"))
      (node (ref "R67") (pin "1") (pinfunction "1_1") (pintype "passive"))
      (node (ref "R68") (pin "1") (pinfunction "1_1") (pintype "passive"))
      (node (ref "R69") (pin "1") (pinfunction "1_1") (pintype "passive"))
      (node (ref "R87") (pin "1") (pinfunction "1_1") (pintype "passive"))
      (node (ref "R90") (pin "1") (pinfunction "1_1") (pintype "passive"))
      (node (ref "R91") (pin "1") (pinfunction "1_1") (pintype "passive"))
      (node (ref "U21") (pin "4") (pinfunction "GND_4") (pintype "passive"))
      (node (ref "U22") (pin "2") (pinfunction "VCC-_2") (pintype "power_in"))
      (node (ref "U23") (pin "2") (pinfunction "VCC-_2") (pintype "power_in"))
      (node (ref "U24") (pin "2") (pinfunction "VCC-_2") (pintype "power_in"))
      (node (ref "U25") (pin "11") (pinfunction "GND_11") (pintype "passive"))
      (node (ref "U26") (pin "11") (pinfunction "GND_11") (pintype "passive"))
    )
    (net (code "17") (name "Net-(D7-PadA)") (class "Default")
      (node (ref "D7") (pin "A") (pinfunction "A_A") (pintype "passive"))
      (node (ref "R65") (pin "1") (pinfunction "1_1") (pintype "passive"))
    )
    (net (code "18") (name "Net-(U21-BOOT)") (class "Default")
      (node (ref "C76") (pin "2") (pinfunction "2_2") (pintype "passive"))
      (node (ref "U21") (pin "6") (pinfunction "BOOT_6") (pintype "passive"))
    )
    (net (code "19") (name "Net-(U21-FB)") (class "Default")
      (node (ref "C81") (pin "1") (pinfunction "1_1") (pintype "passive"))
      (node (ref "R59") (pin "1") (pinfunction "1_1") (pintype "passive"))
      (node (ref "R60") (pin "2") (pinfunction "2_2") (pintype "passive"))
      (node (ref "U21") (pin "8") (pinfunction "FB_8") (pintype "passive"))
    )
    (net (code "20") (name "Net-(U21-RT)") (class "Default")
      (node (ref "R58") (pin "2") (pinfunction "2_2") (pintype "passive"))
      (node (ref "U21") (pin "1") (pinfunction "RT_1") (pintype "passive"))
    )
    (net (code "21") (name "Net-(U21-SS)") (class "Default")
      (node (ref "C75") (pin "2") (pinfunction "2_2") (pintype "passive"))
      (node (ref "U21") (pin "7") (pinfunction "SS_7") (pintype "passive"))
    )
    (net (code "22") (name "Net-(U21-SW)") (class "Default")
      (node (ref "C76") (pin "1") (pinfunction "1_1") (pintype "passive"))
      (node (ref "L5") (pin "1") (pinfunction "1_1") (pintype "passive"))
      (node (ref "U21") (pin "5") (pinfunction "SW_5") (pintype "passive"))
    )
    (net (code "23") (name "Net-(U22-IN+)") (class "Default")
      (node (ref "C72") (pin "2") (pinfunction "2_2") (pintype "passive"))
      (node (ref "R56") (pin "1") (pinfunction "1_1") (pintype "passive"))
      (node (ref "R57") (pin "2") (pinfunction "2_2") (pintype "passive"))
      (node (ref "U22") (pin "3") (pinfunction "IN+_3") (pintype "passive"))
    )
    (net (code "24") (name "Net-(U23-IN-)") (class "Default")
      (node (ref "R98") (pin "1") (pinfunction "1_1") (pintype "passive"))
      (node (ref "U23") (pin "1") (pinfunction "OUT_1") (pintype "passive"))
      (node (ref "U23") (pin "4") (pinfunction "IN-_4") (pintype "passive"))
    )
    (net (code "25") (name "Net-(U24-IN-)") (class "Default")
      (node (ref "R99") (pin "1") (pinfunction "1_1") (pintype "passive"))
      (node (ref "U24") (pin "1") (pinfunction "OUT_1") (pintype "passive"))
      (node (ref "U24") (pin "4") (pinfunction "IN-_4") (pintype "passive"))
    )
    (net (code "26") (name "Net-(U25-IDLY)") (class "Default")
      (node (ref "C86") (pin "2") (pinfunction "2_2") (pintype "passive"))
      (node (ref "U25") (pin "6") (pinfunction "IDLY_6") (pintype "passive"))
    )
    (net (code "27") (name "Net-(U25-ILIM)") (class "Default")
      (node (ref "R66") (pin "2") (pinfunction "2_2") (pintype "passive"))
      (node (ref "U25") (pin "8") (pinfunction "ILIM_8") (pintype "passive"))
    )
    (net (code "28") (name "Net-(U25-OVP)") (class "Default")
      (node (ref "R61") (pin "1") (pinfunction "1_1") (pintype "passive"))
      (node (ref "R62") (pin "2") (pinfunction "2_2") (pintype "passive"))
      (node (ref "U25") (pin "3") (pinfunction "OVP_3") (pintype "passive"))
    )
    (net (code "29") (name "Net-(U25-dV{slash}dT)") (class "Default")
      (node (ref "C84") (pin "2") (pinfunction "2_2") (pintype "passive"))
      (node (ref "U25") (pin "7") (pinfunction "dV/dT_7") (pintype "passive"))
    )
    (net (code "30") (name "Net-(U26-IDLY)") (class "Default")
      (node (ref "C87") (pin "2") (pinfunction "2_2") (pintype "passive"))
      (node (ref "U26") (pin "6") (pinfunction "IDLY_6") (pintype "passive"))
    )
    (net (code "31") (name "Net-(U26-ILIM)") (class "Default")
      (node (ref "R67") (pin "2") (pinfunction "2_2") (pintype "passive"))
      (node (ref "U26") (pin "8") (pinfunction "ILIM_8") (pintype "passive"))
    )
    (net (code "32") (name "Net-(U26-OVP)") (class "Default")
      (node (ref "R63") (pin "1") (pinfunction "1_1") (pintype "passive"))
      (node (ref "R64") (pin "2") (pinfunction "2_2") (pintype "passive"))
      (node (ref "U26") (pin "3") (pinfunction "OVP_3") (pintype "passive"))
    )
    (net (code "33") (name "Net-(U26-dV{slash}dT)") (class "Default")
      (node (ref "C85") (pin "2") (pinfunction "2_2") (pintype "passive"))
      (node (ref "U26") (pin "7") (pinfunction "dV/dT_7") (pintype "passive"))
    )
  )
)
